# OECU_BASE1.net
KiCad netlist of a schematic drawn in Altium Designer
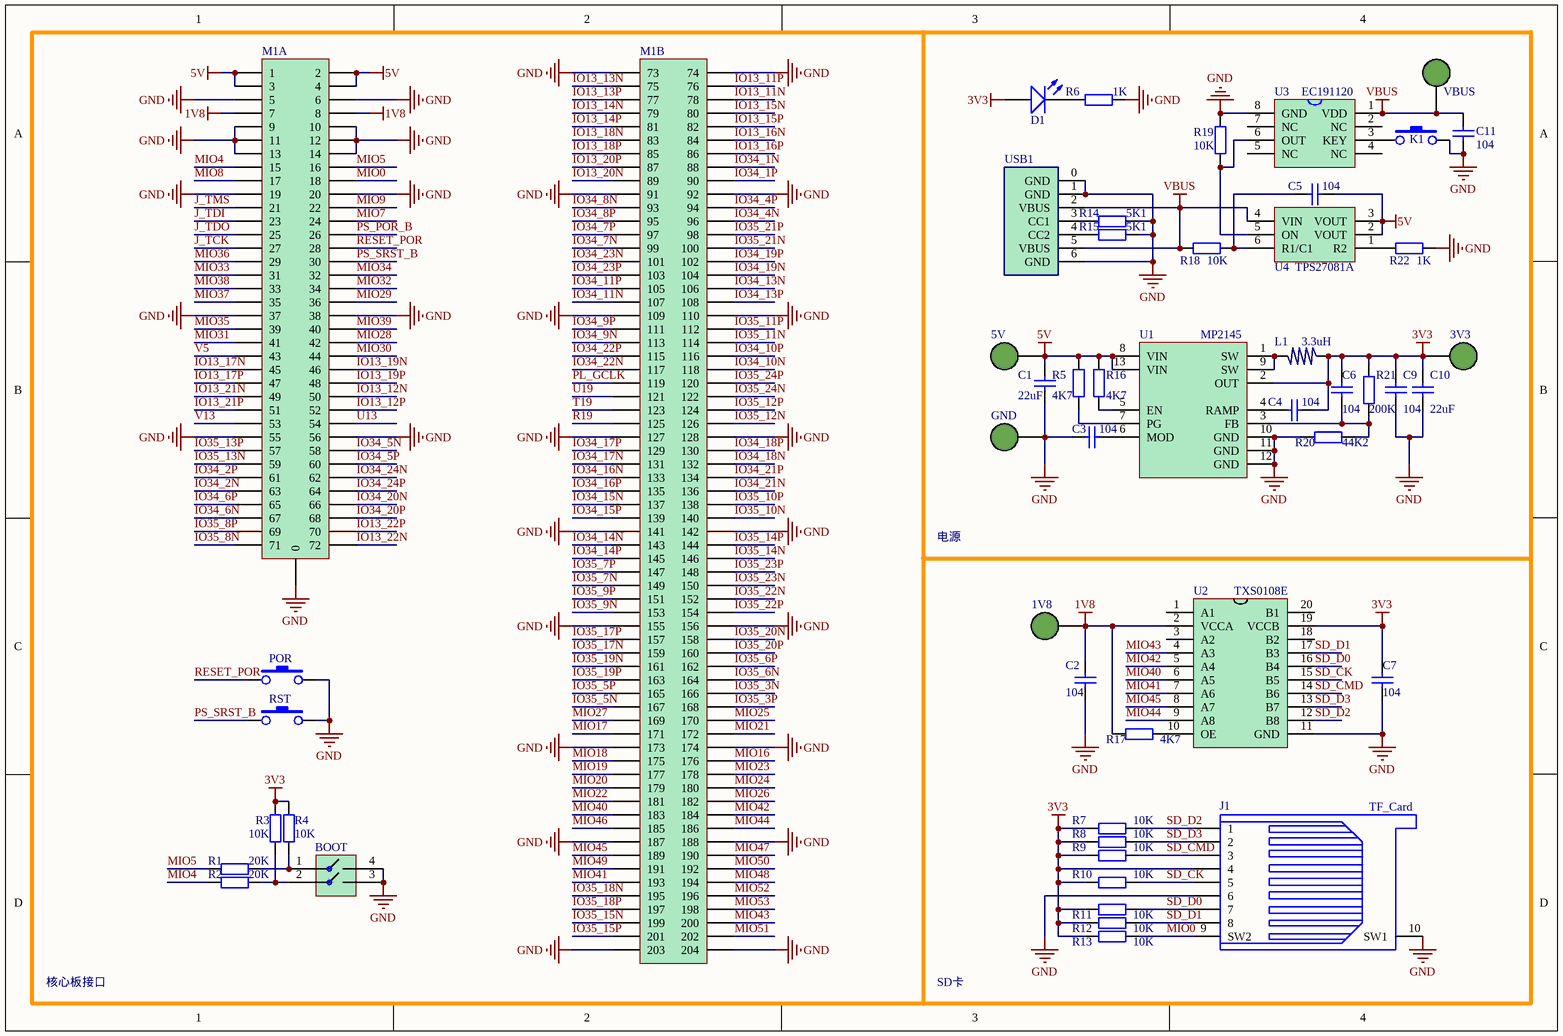
[diagram p0: OECU_BASE1.SchDoc]

(export (version "E")
  (design (tool "Eeschema 10.0.6"))
  (components
    (comp (ref "1V8")
      (value "TEST_POINT_2mm")
      (footprint "TEST_POINT_2mm")
      (libsource (lib "MT_Connector") (part "TEST_POINT_2mm"))
    )
    (comp (ref "3V3")
      (value "TEST_POINT_2mm")
      (footprint "TEST_POINT_2mm")
      (libsource (lib "MT_Connector") (part "TEST_POINT_2mm"))
    )
    (comp (ref "5V")
      (value "TEST_POINT_2mm")
      (footprint "TEST_POINT_2mm")
      (libsource (lib "MT_Connector") (part "TEST_POINT_2mm"))
    )
    (comp (ref "BOOT")
      (value "DIP_SWITCH_2.54_2_SMD_S")
      (footprint "DIP_SWITCH_2.54_2_SMD_S")
      (description "双路贴片立式拨码开关")
      (libsource (lib "MT_Device") (part "DIP_SWITCH_2.54_2_SMD_S"))
    )
    (comp (ref "C1")
      (value "22uF")
      (footprint "1206")
      (description "贴片电容 1206")
      (libsource (lib "MT_Device") (part "CAP_1206"))
    )
    (comp (ref "C2")
      (value "104")
      (footprint "0402")
      (description "贴片电容 0402")
      (libsource (lib "MT_Device") (part "CAP_0402"))
    )
    (comp (ref "C3")
      (value "104")
      (footprint "0402")
      (description "贴片电容 0402")
      (libsource (lib "MT_Device") (part "CAP_0402"))
    )
    (comp (ref "C4")
      (value "104")
      (footprint "0402")
      (description "贴片电容 0402")
      (libsource (lib "MT_Device") (part "CAP_0402"))
    )
    (comp (ref "C5")
      (value "104")
      (footprint "0402")
      (description "贴片电容 0402")
      (libsource (lib "MT_Device") (part "CAP_0402"))
    )
    (comp (ref "C6")
      (value "104")
      (footprint "0402")
      (description "贴片电容 0402")
      (libsource (lib "MT_Device") (part "CAP_0402"))
    )
    (comp (ref "C7")
      (value "104")
      (footprint "0402")
      (description "贴片电容 0402")
      (libsource (lib "MT_Device") (part "CAP_0402"))
    )
    (comp (ref "C9")
      (value "104")
      (footprint "0402")
      (description "贴片电容 0402")
      (libsource (lib "MT_Device") (part "CAP_0402"))
    )
    (comp (ref "C10")
      (value "22uF")
      (footprint "1206")
      (description "贴片电容 1206")
      (libsource (lib "MT_Device") (part "CAP_1206"))
    )
    (comp (ref "C11")
      (value "104")
      (footprint "0402")
      (description "贴片电容 0402")
      (libsource (lib "MT_Device") (part "CAP_0402"))
    )
    (comp (ref "D1")
      (value "LED")
      (footprint "LED_0603")
      (description "LED 0603")
      (libsource (lib "MT_Device") (part "LED_0603"))
    )
    (comp (ref "GND")
      (value "TEST_POINT_2mm")
      (footprint "TEST_POINT_2mm")
      (libsource (lib "MT_Connector") (part "TEST_POINT_2mm"))
    )
    (comp (ref "J1")
      (value "TF_Card")
      (footprint "TF_card")
      (description "TF卡座")
      (libsource (lib "MT_Device") (part "TF_Card"))
    )
    (comp (ref "K1")
      (value "KEY")
      (footprint "KEY_DIP_6_L")
      (description "直插卧式按键 6mm")
      (libsource (lib "MT_Device") (part "KEY_DIP_6_L"))
    )
    (comp (ref "L1")
      (value "3.3uH")
      (footprint "L_0420")
      (description "电感 0420")
      (libsource (lib "MT_Device") (part "L_0420"))
    )
    (comp (ref "M1")
      (value "DDR3_204P_H8")
      (footprint "DDR3_204P_H8")
      (libsource (lib "MT_Connector") (part "DDR3_204P_H8"))
    )
    (comp (ref "POR")
      (value "KEY")
      (footprint "KEY_DIP_6_L")
      (description "直插卧式按键 6mm")
      (libsource (lib "MT_Device") (part "KEY_DIP_6_L"))
    )
    (comp (ref "R1")
      (value "20K")
      (footprint "R_0402")
      (description "电阻 0402")
      (libsource (lib "") (part "RES_0402_1"))
    )
    (comp (ref "R2")
      (value "20K")
      (footprint "R_0402")
      (description "电阻 0402")
      (libsource (lib "") (part "RES_0402_1"))
    )
    (comp (ref "R3")
      (value "10K")
      (footprint "R_0402")
      (description "电阻 0402")
      (libsource (lib "") (part "RES_0402_2"))
    )
    (comp (ref "R4")
      (value "10K")
      (footprint "R_0402")
      (description "电阻 0402")
      (libsource (lib "") (part "RES_0402_2"))
    )
    (comp (ref "R5")
      (value "4K7")
      (footprint "R_0402")
      (description "电阻 0402")
      (libsource (lib "") (part "RES_0402_2"))
    )
    (comp (ref "R6")
      (value "1K")
      (footprint "R_0402")
      (description "电阻 0402")
      (libsource (lib "MT_Device") (part "RES_0402"))
    )
    (comp (ref "R7")
      (value "10K")
      (footprint "R_0402")
      (description "电阻 0402")
      (libsource (lib "MT_Device") (part "RES_0402"))
    )
    (comp (ref "R8")
      (value "10K")
      (footprint "R_0402")
      (description "电阻 0402")
      (libsource (lib "MT_Device") (part "RES_0402"))
    )
    (comp (ref "R9")
      (value "10K")
      (footprint "R_0402")
      (description "电阻 0402")
      (libsource (lib "MT_Device") (part "RES_0402"))
    )
    (comp (ref "R10")
      (value "10K")
      (footprint "R_0402")
      (description "电阻 0402")
      (libsource (lib "MT_Device") (part "RES_0402"))
    )
    (comp (ref "R11")
      (value "10K")
      (footprint "R_0402")
      (description "电阻 0402")
      (libsource (lib "MT_Device") (part "RES_0402"))
    )
    (comp (ref "R12")
      (value "10K")
      (footprint "R_0402")
      (description "电阻 0402")
      (libsource (lib "MT_Device") (part "RES_0402"))
    )
    (comp (ref "R13")
      (value "10K")
      (footprint "R_0402")
      (description "电阻 0402")
      (libsource (lib "MT_Device") (part "RES_0402"))
    )
    (comp (ref "R14")
      (value "5K1")
      (footprint "R_0402")
      (description "电阻 0402")
      (libsource (lib "") (part "RES_0402_1"))
    )
    (comp (ref "R15")
      (value "5K1")
      (footprint "R_0402")
      (description "电阻 0402")
      (libsource (lib "") (part "RES_0402_1"))
    )
    (comp (ref "R16")
      (value "4K7")
      (footprint "R_0402")
      (description "电阻 0402")
      (libsource (lib "") (part "RES_0402_2"))
    )
    (comp (ref "R17")
      (value "4K7")
      (footprint "R_0402")
      (description "电阻 0402")
      (libsource (lib "MT_Device") (part "RES_0402"))
    )
    (comp (ref "R18")
      (value "10K")
      (footprint "R_0402")
      (description "电阻 0402")
      (libsource (lib "") (part "RES_0402_1"))
    )
    (comp (ref "R19")
      (value "10K")
      (footprint "R_0402")
      (description "电阻 0402")
      (libsource (lib "") (part "RES_0402_2"))
    )
    (comp (ref "R20")
      (value "44K2")
      (footprint "R_0402")
      (description "电阻 0402")
      (libsource (lib "") (part "RES_0402_1"))
    )
    (comp (ref "R21")
      (value "200K")
      (footprint "R_0402")
      (description "电阻 0402")
      (libsource (lib "") (part "RES_0402_2"))
    )
    (comp (ref "R22")
      (value "1K")
      (footprint "R_0402")
      (description "电阻 0402")
      (libsource (lib "MT_Device") (part "RES_0402"))
    )
    (comp (ref "RST")
      (value "KEY")
      (footprint "KEY_DIP_6_L")
      (description "直插卧式按键 6mm")
      (libsource (lib "MT_Device") (part "KEY_DIP_6_L"))
    )
    (comp (ref "U1")
      (value "MP2145")
      (footprint "QFN12")
      (description "5.5V, 6A, 1.2MHz")
      (libsource (lib "MT_Chip") (part "MP2145"))
    )
    (comp (ref "U2") (value "TXS0108E") (footprint "TSSOP20") (libsource (lib "MT_Chip") (part "TXS0108E")))
    (comp (ref "U3")
      (value "EC191120")
      (footprint "SOP8-150MIL")
      (description "长按2秒开关机")
      (libsource (lib "MT_Chip") (part "EC191120"))
    )
    (comp (ref "U4")
      (value "TPS27081A")
      (footprint "SOT_23_6")
      (description "高侧负载开关")
      (libsource (lib "MT_Chip") (part "TPS27081A"))
    )
    (comp (ref "USB1")
      (value "USB_C_6P")
      (footprint "USB_C_6PIN")
      (libsource (lib "MT_Device") (part "USB_C_6P"))
    )
    (comp (ref "VBUS")
      (value "TEST_POINT_2mm")
      (footprint "TEST_POINT_2mm")
      (libsource (lib "MT_Connector") (part "TEST_POINT_2mm"))
    )
  )
  (nets
    (net (code "1") (name "/IO13_11N") (class "Default")
      (node (ref "M1") (pin "78") (pinfunction "78_78") (pintype "passive"))
    )
    (net (code "2") (name "/IO13_11P") (class "Default")
      (node (ref "M1") (pin "76") (pinfunction "76_76") (pintype "passive"))
    )
    (net (code "3") (name "/IO13_12N") (class "Default")
      (node (ref "M1") (pin "50") (pinfunction "50_50") (pintype "passive"))
    )
    (net (code "4") (name "/IO13_12P") (class "Default")
      (node (ref "M1") (pin "52") (pinfunction "52_52") (pintype "passive"))
    )
    (net (code "5") (name "/IO13_13N") (class "Default")
      (node (ref "M1") (pin "75") (pinfunction "75_75") (pintype "passive"))
    )
    (net (code "6") (name "/IO13_13P") (class "Default")
      (node (ref "M1") (pin "77") (pinfunction "77_77") (pintype "passive"))
    )
    (net (code "7") (name "/IO13_14N") (class "Default")
      (node (ref "M1") (pin "79") (pinfunction "79_79") (pintype "passive"))
    )
    (net (code "8") (name "/IO13_14P") (class "Default")
      (node (ref "M1") (pin "81") (pinfunction "81_81") (pintype "passive"))
    )
    (net (code "9") (name "/IO13_15N") (class "Default")
      (node (ref "M1") (pin "80") (pinfunction "80_80") (pintype "passive"))
    )
    (net (code "10") (name "/IO13_15P") (class "Default")
      (node (ref "M1") (pin "82") (pinfunction "82_82") (pintype "passive"))
    )
    (net (code "11") (name "/IO13_16N") (class "Default")
      (node (ref "M1") (pin "84") (pinfunction "84_84") (pintype "passive"))
    )
    (net (code "12") (name "/IO13_16P") (class "Default")
      (node (ref "M1") (pin "86") (pinfunction "86_86") (pintype "passive"))
    )
    (net (code "13") (name "/IO13_17N") (class "Default")
      (node (ref "M1") (pin "45") (pinfunction "45_45") (pintype "passive"))
    )
    (net (code "14") (name "/IO13_17P") (class "Default")
      (node (ref "M1") (pin "47") (pinfunction "47_47") (pintype "passive"))
    )
    (net (code "15") (name "/IO13_18N") (class "Default")
      (node (ref "M1") (pin "83") (pinfunction "83_83") (pintype "passive"))
    )
    (net (code "16") (name "/IO13_18P") (class "Default")
      (node (ref "M1") (pin "85") (pinfunction "85_85") (pintype "passive"))
    )
    (net (code "17") (name "/IO13_19N") (class "Default")
      (node (ref "M1") (pin "46") (pinfunction "46_46") (pintype "passive"))
    )
    (net (code "18") (name "/IO13_19P") (class "Default")
      (node (ref "M1") (pin "48") (pinfunction "48_48") (pintype "passive"))
    )
    (net (code "19") (name "/IO13_20N") (class "Default")
      (node (ref "M1") (pin "89") (pinfunction "89_89") (pintype "passive"))
    )
    (net (code "20") (name "/IO13_20P") (class "Default")
      (node (ref "M1") (pin "87") (pinfunction "87_87") (pintype "passive"))
    )
    (net (code "21") (name "/IO13_21N") (class "Default")
      (node (ref "M1") (pin "49") (pinfunction "49_49") (pintype "passive"))
    )
    (net (code "22") (name "/IO13_21P") (class "Default")
      (node (ref "M1") (pin "51") (pinfunction "51_51") (pintype "passive"))
    )
    (net (code "23") (name "/IO13_22N") (class "Default")
      (node (ref "M1") (pin "72") (pinfunction "72_72") (pintype "passive"))
    )
    (net (code "24") (name "/IO13_22P") (class "Default")
      (node (ref "M1") (pin "70") (pinfunction "70_70") (pintype "passive"))
    )
    (net (code "25") (name "/IO34_1N") (class "Default")
      (node (ref "M1") (pin "88") (pinfunction "88_88") (pintype "passive"))
    )
    (net (code "26") (name "/IO34_1P") (class "Default")
      (node (ref "M1") (pin "90") (pinfunction "90_90") (pintype "passive"))
    )
    (net (code "27") (name "/IO34_2N") (class "Default")
      (node (ref "M1") (pin "63") (pinfunction "63_63") (pintype "passive"))
    )
    (net (code "28") (name "/IO34_2P") (class "Default")
      (node (ref "M1") (pin "61") (pinfunction "61_61") (pintype "passive"))
    )
    (net (code "29") (name "/IO34_4N") (class "Default")
      (node (ref "M1") (pin "96") (pinfunction "96_96") (pintype "passive"))
    )
    (net (code "30") (name "/IO34_4P") (class "Default")
      (node (ref "M1") (pin "94") (pinfunction "94_94") (pintype "passive"))
    )
    (net (code "31") (name "/IO34_5N") (class "Default")
      (node (ref "M1") (pin "58") (pinfunction "58_58") (pintype "passive"))
    )
    (net (code "32") (name "/IO34_5P") (class "Default")
      (node (ref "M1") (pin "60") (pinfunction "60_60") (pintype "passive"))
    )
    (net (code "33") (name "/IO34_6N") (class "Default")
      (node (ref "M1") (pin "67") (pinfunction "67_67") (pintype "passive"))
    )
    (net (code "34") (name "/IO34_6P") (class "Default")
      (node (ref "M1") (pin "65") (pinfunction "65_65") (pintype "passive"))
    )
    (net (code "35") (name "/IO34_7N") (class "Default")
      (node (ref "M1") (pin "99") (pinfunction "99_99") (pintype "passive"))
    )
    (net (code "36") (name "/IO34_7P") (class "Default")
      (node (ref "M1") (pin "97") (pinfunction "97_97") (pintype "passive"))
    )
    (net (code "37") (name "/IO34_8N") (class "Default")
      (node (ref "M1") (pin "93") (pinfunction "93_93") (pintype "passive"))
    )
    (net (code "38") (name "/IO34_8P") (class "Default")
      (node (ref "M1") (pin "95") (pinfunction "95_95") (pintype "passive"))
    )
    (net (code "39") (name "/IO34_9N") (class "Default")
      (node (ref "M1") (pin "113") (pinfunction "113_113") (pintype "passive"))
    )
    (net (code "40") (name "/IO34_9P") (class "Default")
      (node (ref "M1") (pin "111") (pinfunction "111_111") (pintype "passive"))
    )
    (net (code "41") (name "/IO34_10N") (class "Default")
      (node (ref "M1") (pin "118") (pinfunction "118_118") (pintype "passive"))
    )
    (net (code "42") (name "/IO34_10P") (class "Default")
      (node (ref "M1") (pin "116") (pinfunction "116_116") (pintype "passive"))
    )
    (net (code "43") (name "/IO34_11N") (class "Default")
      (node (ref "M1") (pin "107") (pinfunction "107_107") (pintype "passive"))
    )
    (net (code "44") (name "/IO34_11P") (class "Default")
      (node (ref "M1") (pin "105") (pinfunction "105_105") (pintype "passive"))
    )
    (net (code "45") (name "/IO34_13N") (class "Default")
      (node (ref "M1") (pin "106") (pinfunction "106_106") (pintype "passive"))
    )
    (net (code "46") (name "/IO34_13P") (class "Default")
      (node (ref "M1") (pin "108") (pinfunction "108_108") (pintype "passive"))
    )
    (net (code "47") (name "/IO34_14N") (class "Default")
      (node (ref "M1") (pin "143") (pinfunction "143_143") (pintype "passive"))
    )
    (net (code "48") (name "/IO34_14P") (class "Default")
      (node (ref "M1") (pin "145") (pinfunction "145_145") (pintype "passive"))
    )
    (net (code "49") (name "/IO34_15N") (class "Default")
      (node (ref "M1") (pin "137") (pinfunction "137_137") (pintype "passive"))
    )
    (net (code "50") (name "/IO34_15P") (class "Default")
      (node (ref "M1") (pin "139") (pinfunction "139_139") (pintype "passive"))
    )
    (net (code "51") (name "/IO34_16N") (class "Default")
      (node (ref "M1") (pin "133") (pinfunction "133_133") (pintype "passive"))
    )
    (net (code "52") (name "/IO34_16P") (class "Default")
      (node (ref "M1") (pin "135") (pinfunction "135_135") (pintype "passive"))
    )
    (net (code "53") (name "/IO34_17N") (class "Default")
      (node (ref "M1") (pin "131") (pinfunction "131_131") (pintype "passive"))
    )
    (net (code "54") (name "/IO34_17P") (class "Default")
      (node (ref "M1") (pin "129") (pinfunction "129_129") (pintype "passive"))
    )
    (net (code "55") (name "/IO34_18N") (class "Default")
      (node (ref "M1") (pin "132") (pinfunction "132_132") (pintype "passive"))
    )
    (net (code "56") (name "/IO34_18P") (class "Default")
      (node (ref "M1") (pin "130") (pinfunction "130_130") (pintype "passive"))
    )
    (net (code "57") (name "/IO34_19N") (class "Default")
      (node (ref "M1") (pin "104") (pinfunction "104_104") (pintype "passive"))
    )
    (net (code "58") (name "/IO34_19P") (class "Default")
      (node (ref "M1") (pin "102") (pinfunction "102_102") (pintype "passive"))
    )
    (net (code "59") (name "/IO34_20N") (class "Default")
      (node (ref "M1") (pin "66") (pinfunction "66_66") (pintype "passive"))
    )
    (net (code "60") (name "/IO34_20P") (class "Default")
      (node (ref "M1") (pin "68") (pinfunction "68_68") (pintype "passive"))
    )
    (net (code "61") (name "/IO34_21N") (class "Default")
      (node (ref "M1") (pin "136") (pinfunction "136_136") (pintype "passive"))
    )
    (net (code "62") (name "/IO34_21P") (class "Default")
      (node (ref "M1") (pin "134") (pinfunction "134_134") (pintype "passive"))
    )
    (net (code "63") (name "/IO34_22N") (class "Default")
      (node (ref "M1") (pin "117") (pinfunction "117_117") (pintype "passive"))
    )
    (net (code "64") (name "/IO34_22P") (class "Default")
      (node (ref "M1") (pin "115") (pinfunction "115_115") (pintype "passive"))
    )
    (net (code "65") (name "/IO34_23N") (class "Default")
      (node (ref "M1") (pin "101") (pinfunction "101_101") (pintype "passive"))
    )
    (net (code "66") (name "/IO34_23P") (class "Default")
      (node (ref "M1") (pin "103") (pinfunction "103_103") (pintype "passive"))
    )
    (net (code "67") (name "/IO34_24N") (class "Default")
      (node (ref "M1") (pin "62") (pinfunction "62_62") (pintype "passive"))
    )
    (net (code "68") (name "/IO34_24P") (class "Default")
      (node (ref "M1") (pin "64") (pinfunction "64_64") (pintype "passive"))
    )
    (net (code "69") (name "/IO35_3N") (class "Default")
      (node (ref "M1") (pin "166") (pinfunction "166_166") (pintype "passive"))
    )
    (net (code "70") (name "/IO35_3P") (class "Default")
      (node (ref "M1") (pin "168") (pinfunction "168_168") (pintype "passive"))
    )
    (net (code "71") (name "/IO35_5N") (class "Default")
      (node (ref "M1") (pin "167") (pinfunction "167_167") (pintype "passive"))
    )
    (net (code "72") (name "/IO35_5P") (class "Default")
      (node (ref "M1") (pin "165") (pinfunction "165_165") (pintype "passive"))
    )
    (net (code "73") (name "/IO35_6N") (class "Default")
      (node (ref "M1") (pin "164") (pinfunction "164_164") (pintype "passive"))
    )
    (net (code "74") (name "/IO35_6P") (class "Default")
      (node (ref "M1") (pin "162") (pinfunction "162_162") (pintype "passive"))
    )
    (net (code "75") (name "/IO35_7N") (class "Default")
      (node (ref "M1") (pin "149") (pinfunction "149_149") (pintype "passive"))
    )
    (net (code "76") (name "/IO35_7P") (class "Default")
      (node (ref "M1") (pin "147") (pinfunction "147_147") (pintype "passive"))
    )
    (net (code "77") (name "/IO35_8N") (class "Default")
      (node (ref "M1") (pin "71") (pinfunction "71_71") (pintype "passive"))
    )
    (net (code "78") (name "/IO35_8P") (class "Default")
      (node (ref "M1") (pin "69") (pinfunction "69_69") (pintype "passive"))
    )
    (net (code "79") (name "/IO35_9N") (class "Default")
      (node (ref "M1") (pin "153") (pinfunction "153_153") (pintype "passive"))
    )
    (net (code "80") (name "/IO35_9P") (class "Default")
      (node (ref "M1") (pin "151") (pinfunction "151_151") (pintype "passive"))
    )
    (net (code "81") (name "/IO35_10N") (class "Default")
      (node (ref "M1") (pin "140") (pinfunction "140_140") (pintype "passive"))
    )
    (net (code "82") (name "/IO35_10P") (class "Default")
      (node (ref "M1") (pin "138") (pinfunction "138_138") (pintype "passive"))
    )
    (net (code "83") (name "/IO35_11N") (class "Default")
      (node (ref "M1") (pin "114") (pinfunction "114_114") (pintype "passive"))
    )
    (net (code "84") (name "/IO35_11P") (class "Default")
      (node (ref "M1") (pin "112") (pinfunction "112_112") (pintype "passive"))
    )
    (net (code "85") (name "/IO35_12N") (class "Default")
      (node (ref "M1") (pin "126") (pinfunction "126_126") (pintype "passive"))
    )
    (net (code "86") (name "/IO35_12P") (class "Default")
      (node (ref "M1") (pin "124") (pinfunction "124_124") (pintype "passive"))
    )
    (net (code "87") (name "/IO35_13N") (class "Default")
      (node (ref "M1") (pin "59") (pinfunction "59_59") (pintype "passive"))
    )
    (net (code "88") (name "/IO35_13P") (class "Default")
      (node (ref "M1") (pin "57") (pinfunction "57_57") (pintype "passive"))
    )
    (net (code "89") (name "/IO35_14N") (class "Default")
      (node (ref "M1") (pin "146") (pinfunction "146_146") (pintype "passive"))
    )
    (net (code "90") (name "/IO35_14P") (class "Default")
      (node (ref "M1") (pin "144") (pinfunction "144_144") (pintype "passive"))
    )
    (net (code "91") (name "/IO35_15N") (class "Default")
      (node (ref "M1") (pin "199") (pinfunction "199_199") (pintype "passive"))
    )
    (net (code "92") (name "/IO35_15P") (class "Default")
      (node (ref "M1") (pin "201") (pinfunction "201_201") (pintype "passive"))
    )
    (net (code "93") (name "/IO35_17N") (class "Default")
      (node (ref "M1") (pin "159") (pinfunction "159_159") (pintype "passive"))
    )
    (net (code "94") (name "/IO35_17P") (class "Default")
      (node (ref "M1") (pin "157") (pinfunction "157_157") (pintype "passive"))
    )
    (net (code "95") (name "/IO35_18N") (class "Default")
      (node (ref "M1") (pin "195") (pinfunction "195_195") (pintype "passive"))
    )
    (net (code "96") (name "/IO35_18P") (class "Default")
      (node (ref "M1") (pin "197") (pinfunction "197_197") (pintype "passive"))
    )
    (net (code "97") (name "/IO35_19N") (class "Default")
      (node (ref "M1") (pin "161") (pinfunction "161_161") (pintype "passive"))
    )
    (net (code "98") (name "/IO35_19P") (class "Default")
      (node (ref "M1") (pin "163") (pinfunction "163_163") (pintype "passive"))
    )
    (net (code "99") (name "/IO35_20N") (class "Default")
      (node (ref "M1") (pin "158") (pinfunction "158_158") (pintype "passive"))
    )
    (net (code "100") (name "/IO35_20P") (class "Default")
      (node (ref "M1") (pin "160") (pinfunction "160_160") (pintype "passive"))
    )
    (net (code "101") (name "/IO35_21N") (class "Default")
      (node (ref "M1") (pin "100") (pinfunction "100_100") (pintype "passive"))
    )
    (net (code "102") (name "/IO35_21P") (class "Default")
      (node (ref "M1") (pin "98") (pinfunction "98_98") (pintype "passive"))
    )
    (net (code "103") (name "/IO35_22N") (class "Default")
      (node (ref "M1") (pin "152") (pinfunction "152_152") (pintype "passive"))
    )
    (net (code "104") (name "/IO35_22P") (class "Default")
      (node (ref "M1") (pin "154") (pinfunction "154_154") (pintype "passive"))
    )
    (net (code "105") (name "/IO35_23N") (class "Default")
      (node (ref "M1") (pin "150") (pinfunction "150_150") (pintype "passive"))
    )
    (net (code "106") (name "/IO35_23P") (class "Default")
      (node (ref "M1") (pin "148") (pinfunction "148_148") (pintype "passive"))
    )
    (net (code "107") (name "/IO35_24N") (class "Default")
      (node (ref "M1") (pin "122") (pinfunction "122_122") (pintype "passive"))
    )
    (net (code "108") (name "/IO35_24P") (class "Default")
      (node (ref "M1") (pin "120") (pinfunction "120_120") (pintype "passive"))
    )
    (net (code "109") (name "/J_TCK") (class "Default")
      (node (ref "M1") (pin "27") (pinfunction "27_27") (pintype "passive"))
    )
    (net (code "110") (name "/J_TDI") (class "Default")
      (node (ref "M1") (pin "23") (pinfunction "23_23") (pintype "passive"))
    )
    (net (code "111") (name "/J_TDO") (class "Default")
      (node (ref "M1") (pin "25") (pinfunction "25_25") (pintype "passive"))
    )
    (net (code "112") (name "/J_TMS") (class "Default")
      (node (ref "M1") (pin "21") (pinfunction "21_21") (pintype "passive"))
    )
    (net (code "113") (name "/MIO0") (class "Default")
      (node (ref "J1") (pin "9") (pinfunction "SW2_9") (pintype "passive"))
      (node (ref "M1") (pin "18") (pinfunction "18_18") (pintype "passive"))
      (node (ref "R13") (pin "2") (pinfunction "2_2") (pintype "passive"))
    )
    (net (code "114") (name "/MIO4") (class "Default")
      (node (ref "M1") (pin "15") (pinfunction "15_15") (pintype "passive"))
      (node (ref "R2") (pin "2") (pinfunction "2_2") (pintype "passive"))
    )
    (net (code "115") (name "/MIO5") (class "Default")
      (node (ref "M1") (pin "16") (pinfunction "16_16") (pintype "passive"))
      (node (ref "R1") (pin "2") (pinfunction "2_2") (pintype "passive"))
    )
    (net (code "116") (name "/MIO7") (class "Default")
      (node (ref "M1") (pin "24") (pinfunction "24_24") (pintype "passive"))
    )
    (net (code "117") (name "/MIO8") (class "Default")
      (node (ref "M1") (pin "17") (pinfunction "17_17") (pintype "passive"))
    )
    (net (code "118") (name "/MIO9") (class "Default")
      (node (ref "M1") (pin "22") (pinfunction "22_22") (pintype "passive"))
    )
    (net (code "119") (name "/MIO16") (class "Default")
      (node (ref "M1") (pin "176") (pinfunction "176_176") (pintype "passive"))
    )
    (net (code "120") (name "/MIO17") (class "Default")
      (node (ref "M1") (pin "171") (pinfunction "171_171") (pintype "passive"))
    )
    (net (code "121") (name "/MIO18") (class "Default")
      (node (ref "M1") (pin "175") (pinfunction "175_175") (pintype "passive"))
    )
    (net (code "122") (name "/MIO19") (class "Default")
      (node (ref "M1") (pin "177") (pinfunction "177_177") (pintype "passive"))
    )
    (net (code "123") (name "/MIO20") (class "Default")
      (node (ref "M1") (pin "179") (pinfunction "179_179") (pintype "passive"))
    )
    (net (code "124") (name "/MIO21") (class "Default")
      (node (ref "M1") (pin "172") (pinfunction "172_172") (pintype "passive"))
    )
    (net (code "125") (name "/MIO22") (class "Default")
      (node (ref "M1") (pin "181") (pinfunction "181_181") (pintype "passive"))
    )
    (net (code "126") (name "/MIO23") (class "Default")
      (node (ref "M1") (pin "178") (pinfunction "178_178") (pintype "passive"))
    )
    (net (code "127") (name "/MIO24") (class "Default")
      (node (ref "M1") (pin "180") (pinfunction "180_180") (pintype "passive"))
    )
    (net (code "128") (name "/MIO25") (class "Default")
      (node (ref "M1") (pin "170") (pinfunction "170_170") (pintype "passive"))
    )
    (net (code "129") (name "/MIO26") (class "Default")
      (node (ref "M1") (pin "182") (pinfunction "182_182") (pintype "passive"))
    )
    (net (code "130") (name "/MIO27") (class "Default")
      (node (ref "M1") (pin "169") (pinfunction "169_169") (pintype "passive"))
    )
    (net (code "131") (name "/MIO28") (class "Default")
      (node (ref "M1") (pin "42") (pinfunction "42_42") (pintype "passive"))
    )
    (net (code "132") (name "/MIO29") (class "Default")
      (node (ref "M1") (pin "36") (pinfunction "36_36") (pintype "passive"))
    )
    (net (code "133") (name "/MIO30") (class "Default")
      (node (ref "M1") (pin "44") (pinfunction "44_44") (pintype "passive"))
    )
    (net (code "134") (name "/MIO31") (class "Default")
      (node (ref "M1") (pin "41") (pinfunction "41_41") (pintype "passive"))
    )
    (net (code "135") (name "/MIO32") (class "Default")
      (node (ref "M1") (pin "34") (pinfunction "34_34") (pintype "passive"))
    )
    (net (code "136") (name "/MIO33") (class "Default")
      (node (ref "M1") (pin "31") (pinfunction "31_31") (pintype "passive"))
    )
    (net (code "137") (name "/MIO34") (class "Default")
      (node (ref "M1") (pin "32") (pinfunction "32_32") (pintype "passive"))
    )
    (net (code "138") (name "/MIO35") (class "Default")
      (node (ref "M1") (pin "39") (pinfunction "39_39") (pintype "passive"))
    )
    (net (code "139") (name "/MIO36") (class "Default")
      (node (ref "M1") (pin "29") (pinfunction "29_29") (pintype "passive"))
    )
    (net (code "140") (name "/MIO37") (class "Default")
      (node (ref "M1") (pin "35") (pinfunction "35_35") (pintype "passive"))
    )
    (net (code "141") (name "/MIO38") (class "Default")
      (node (ref "M1") (pin "33") (pinfunction "33_33") (pintype "passive"))
    )
    (net (code "142") (name "/MIO39") (class "Default")
      (node (ref "M1") (pin "40") (pinfunction "40_40") (pintype "passive"))
    )
    (net (code "143") (name "/MIO40") (class "Default")
      (node (ref "M1") (pin "183") (pinfunction "183_183") (pintype "passive"))
      (node (ref "U2") (pin "6") (pinfunction "A5_6") (pintype "passive"))
    )
    (net (code "144") (name "/MIO41") (class "Default")
      (node (ref "M1") (pin "193") (pinfunction "193_193") (pintype "passive"))
      (node (ref "U2") (pin "7") (pinfunction "A6_7") (pintype "passive"))
    )
    (net (code "145") (name "/MIO42") (class "Default")
      (node (ref "M1") (pin "184") (pinfunction "184_184") (pintype "passive"))
      (node (ref "U2") (pin "5") (pinfunction "A4_5") (pintype "passive"))
    )
    (net (code "146") (name "/MIO43") (class "Default")
      (node (ref "M1") (pin "200") (pinfunction "200_200") (pintype "passive"))
      (node (ref "U2") (pin "4") (pinfunction "A3_4") (pintype "passive"))
    )
    (net (code "147") (name "/MIO44") (class "Default")
      (node (ref "M1") (pin "186") (pinfunction "186_186") (pintype "passive"))
      (node (ref "U2") (pin "9") (pinfunction "A8_9") (pintype "passive"))
    )
    (net (code "148") (name "/MIO45") (class "Default")
      (node (ref "M1") (pin "189") (pinfunction "189_189") (pintype "passive"))
      (node (ref "U2") (pin "8") (pinfunction "A7_8") (pintype "passive"))
    )
    (net (code "149") (name "/MIO46") (class "Default")
      (node (ref "M1") (pin "185") (pinfunction "185_185") (pintype "passive"))
    )
    (net (code "150") (name "/MIO47") (class "Default")
      (node (ref "M1") (pin "190") (pinfunction "190_190") (pintype "passive"))
    )
    (net (code "151") (name "/MIO48") (class "Default")
      (node (ref "M1") (pin "194") (pinfunction "194_194") (pintype "passive"))
    )
    (net (code "152") (name "/MIO49") (class "Default")
      (node (ref "M1") (pin "191") (pinfunction "191_191") (pintype "passive"))
    )
    (net (code "153") (name "/MIO50") (class "Default")
      (node (ref "M1") (pin "192") (pinfunction "192_192") (pintype "passive"))
    )
    (net (code "154") (name "/MIO51") (class "Default")
      (node (ref "M1") (pin "202") (pinfunction "202_202") (pintype "passive"))
    )
    (net (code "155") (name "/MIO52") (class "Default")
      (node (ref "M1") (pin "196") (pinfunction "196_196") (pintype "passive"))
    )
    (net (code "156") (name "/MIO53") (class "Default")
      (node (ref "M1") (pin "198") (pinfunction "198_198") (pintype "passive"))
    )
    (net (code "157") (name "/PL_GCLK") (class "Default")
      (node (ref "M1") (pin "119") (pinfunction "119_119") (pintype "passive"))
    )
    (net (code "158") (name "/PS_POR_B") (class "Default")
      (node (ref "M1") (pin "26") (pinfunction "26_26") (pintype "passive"))
    )
    (net (code "159") (name "/PS_SRST_B") (class "Default")
      (node (ref "M1") (pin "30") (pinfunction "30_30") (pintype "passive"))
      (node (ref "RST") (pin "2") (pinfunction "2_2") (pintype "passive"))
    )
    (net (code "160") (name "/R19") (class "Default")
      (node (ref "M1") (pin "125") (pinfunction "125_125") (pintype "passive"))
    )
    (net (code "161") (name "/RESET_POR") (class "Default")
      (node (ref "M1") (pin "28") (pinfunction "28_28") (pintype "passive"))
      (node (ref "POR") (pin "2") (pinfunction "2_2") (pintype "passive"))
    )
    (net (code "162") (name "/SD_CK") (class "Default")
      (node (ref "J1") (pin "5") (pinfunction "5_5") (pintype "passive"))
      (node (ref "R10") (pin "2") (pinfunction "2_2") (pintype "passive"))
      (node (ref "U2") (pin "15") (pinfunction "B5_15") (pintype "passive"))
    )
    (net (code "163") (name "/SD_CMD") (class "Default")
      (node (ref "J1") (pin "3") (pinfunction "3_3") (pintype "passive"))
      (node (ref "R9") (pin "2") (pinfunction "2_2") (pintype "passive"))
      (node (ref "U2") (pin "14") (pinfunction "B6_14") (pintype "passive"))
    )
    (net (code "164") (name "/SD_D0") (class "Default")
      (node (ref "J1") (pin "7") (pinfunction "7_7") (pintype "passive"))
      (node (ref "R11") (pin "2") (pinfunction "2_2") (pintype "passive"))
      (node (ref "U2") (pin "16") (pinfunction "B4_16") (pintype "passive"))
    )
    (net (code "165") (name "/SD_D1") (class "Default")
      (node (ref "J1") (pin "8") (pinfunction "8_8") (pintype "passive"))
      (node (ref "R12") (pin "2") (pinfunction "2_2") (pintype "passive"))
      (node (ref "U2") (pin "17") (pinfunction "B3_17") (pintype "passive"))
    )
    (net (code "166") (name "/SD_D2") (class "Default")
      (node (ref "J1") (pin "1") (pinfunction "1_1") (pintype "passive"))
      (node (ref "R7") (pin "2") (pinfunction "2_2") (pintype "passive"))
      (node (ref "U2") (pin "12") (pinfunction "B8_12") (pintype "passive"))
    )
    (net (code "167") (name "/SD_D3") (class "Default")
      (node (ref "J1") (pin "2") (pinfunction "2_2") (pintype "passive"))
      (node (ref "R8") (pin "2") (pinfunction "2_2") (pintype "passive"))
      (node (ref "U2") (pin "13") (pinfunction "B7_13") (pintype "passive"))
    )
    (net (code "168") (name "/T19") (class "Default")
      (node (ref "M1") (pin "123") (pinfunction "123_123") (pintype "passive"))
    )
    (net (code "169") (name "/U13") (class "Default")
      (node (ref "M1") (pin "54") (pinfunction "54_54") (pintype "passive"))
    )
    (net (code "170") (name "/U19") (class "Default")
      (node (ref "M1") (pin "121") (pinfunction "121_121") (pintype "passive"))
    )
    (net (code "171") (name "/V5") (class "Default")
      (node (ref "M1") (pin "43") (pinfunction "43_43") (pintype "passive"))
    )
    (net (code "172") (name "/V13") (class "Default")
      (node (ref "M1") (pin "53") (pinfunction "53_53") (pintype "passive"))
    )
    (net (code "173") (name "1V8") (class "Default")
      (node (ref "1V8") (pin "1") (pinfunction "1_1") (pintype "passive"))
      (node (ref "C2") (pin "2") (pinfunction "2_2") (pintype "passive"))
      (node (ref "M1") (pin "7") (pinfunction "7_7") (pintype "passive"))
      (node (ref "M1") (pin "8") (pinfunction "8_8") (pintype "passive"))
      (node (ref "R17") (pin "1") (pinfunction "1_1") (pintype "passive"))
      (node (ref "U2") (pin "2") (pinfunction "VCCA_2") (pintype "passive"))
    )
    (net (code "174") (name "3V3") (class "Default")
      (node (ref "3V3") (pin "1") (pinfunction "1_1") (pintype "passive"))
      (node (ref "C10") (pin "2") (pinfunction "2_2") (pintype "passive"))
      (node (ref "C4") (pin "2") (pinfunction "2_2") (pintype "passive"))
      (node (ref "C6") (pin "2") (pinfunction "2_2") (pintype "passive"))
      (node (ref "C7") (pin "2") (pinfunction "2_2") (pintype "passive"))
      (node (ref "C9") (pin "2") (pinfunction "2_2") (pintype "passive"))
      (node (ref "D1") (pin "A") (pinfunction "A_A") (pintype "passive"))
      (node (ref "J1") (pin "4") (pinfunction "4_4") (pintype "passive"))
      (node (ref "L1") (pin "1") (pintype "passive"))
      (node (ref "R10") (pin "1") (pinfunction "1_1") (pintype "passive"))
      (node (ref "R11") (pin "1") (pinfunction "1_1") (pintype "passive"))
      (node (ref "R12") (pin "1") (pinfunction "1_1") (pintype "passive"))
      (node (ref "R13") (pin "1") (pinfunction "1_1") (pintype "passive"))
      (node (ref "R21") (pin "2") (pinfunction "2_2") (pintype "passive"))
      (node (ref "R3") (pin "2") (pinfunction "2_2") (pintype "passive"))
      (node (ref "R4") (pin "2") (pinfunction "2_2") (pintype "passive"))
      (node (ref "R7") (pin "1") (pinfunction "1_1") (pintype "passive"))
      (node (ref "R8") (pin "1") (pinfunction "1_1") (pintype "passive"))
      (node (ref "R9") (pin "1") (pinfunction "1_1") (pintype "passive"))
      (node (ref "U1") (pin "2") (pinfunction "OUT_2") (pintype "passive"))
      (node (ref "U2") (pin "19") (pinfunction "VCCB_19") (pintype "passive"))
    )
    (net (code "175") (name "5V") (class "Default")
      (node (ref "5V") (pin "1") (pinfunction "1_1") (pintype "passive"))
      (node (ref "C1") (pin "2") (pinfunction "2_2") (pintype "passive"))
      (node (ref "C5") (pin "1") (pinfunction "1_1") (pintype "passive"))
      (node (ref "M1") (pin "1") (pinfunction "1_1") (pintype "passive"))
      (node (ref "M1") (pin "2") (pinfunction "2_2") (pintype "passive"))
      (node (ref "M1") (pin "3") (pinfunction "3_3") (pintype "passive"))
      (node (ref "M1") (pin "4") (pinfunction "4_4") (pintype "passive"))
      (node (ref "R16") (pin "2") (pinfunction "2_2") (pintype "passive"))
      (node (ref "R5") (pin "2") (pinfunction "2_2") (pintype "passive"))
      (node (ref "U1") (pin "13") (pinfunction "VIN_13") (pintype "passive"))
      (node (ref "U1") (pin "8") (pinfunction "VIN_8") (pintype "passive"))
      (node (ref "U4") (pin "2") (pinfunction "VOUT_2") (pintype "passive"))
      (node (ref "U4") (pin "3") (pinfunction "VOUT_3") (pintype "passive"))
    )
    (net (code "176") (name "GND") (class "Default")
      (node (ref "BOOT") (pin "3") (pinfunction "3_3") (pintype "passive"))
      (node (ref "BOOT") (pin "4") (pinfunction "4_4") (pintype "passive"))
      (node (ref "C1") (pin "1") (pinfunction "1_1") (pintype "passive"))
      (node (ref "C10") (pin "1") (pinfunction "1_1") (pintype "passive"))
      (node (ref "C11") (pin "2") (pinfunction "2_2") (pintype "passive"))
      (node (ref "C2") (pin "1") (pinfunction "1_1") (pintype "passive"))
      (node (ref "C3") (pin "2") (pinfunction "2_2") (pintype "passive"))
      (node (ref "C7") (pin "1") (pinfunction "1_1") (pintype "passive"))
      (node (ref "C9") (pin "1") (pinfunction "1_1") (pintype "passive"))
      (node (ref "GND") (pin "1") (pinfunction "1_1") (pintype "passive"))
      (node (ref "J1") (pin "10") (pinfunction "SW1_10") (pintype "passive"))
      (node (ref "J1") (pin "6") (pinfunction "6_6") (pintype "passive"))
      (node (ref "K1") (pin "1") (pinfunction "1_1") (pintype "passive"))
      (node (ref "M1") (pin "0") (pinfunction "0_0") (pintype "passive"))
      (node (ref "M1") (pin "10") (pinfunction "10_10") (pintype "passive"))
      (node (ref "M1") (pin "109") (pinfunction "109_109") (pintype "passive"))
      (node (ref "M1") (pin "11") (pinfunction "11_11") (pintype "passive"))
      (node (ref "M1") (pin "110") (pinfunction "110_110") (pintype "passive"))
      (node (ref "M1") (pin "12") (pinfunction "12_12") (pintype "passive"))
      (node (ref "M1") (pin "127") (pinfunction "127_127") (pintype "passive"))
      (node (ref "M1") (pin "128") (pinfunction "128_128") (pintype "passive"))
      (node (ref "M1") (pin "13") (pinfunction "13_13") (pintype "passive"))
      (node (ref "M1") (pin "14") (pinfunction "14_14") (pintype "passive"))
      (node (ref "M1") (pin "141") (pinfunction "141_141") (pintype "passive"))
      (node (ref "M1") (pin "142") (pinfunction "142_142") (pintype "passive"))
      (node (ref "M1") (pin "155") (pinfunction "155_155") (pintype "passive"))
      (node (ref "M1") (pin "156") (pinfunction "156_156") (pintype "passive"))
      (node (ref "M1") (pin "173") (pinfunction "173_173") (pintype "passive"))
      (node (ref "M1") (pin "174") (pinfunction "174_174") (pintype "passive"))
      (node (ref "M1") (pin "187") (pinfunction "187_187") (pintype "passive"))
      (node (ref "M1") (pin "188") (pinfunction "188_188") (pintype "passive"))
      (node (ref "M1") (pin "19") (pinfunction "19_19") (pintype "passive"))
      (node (ref "M1") (pin "20") (pinfunction "20_20") (pintype "passive"))
      (node (ref "M1") (pin "203") (pinfunction "203_203") (pintype "passive"))
      (node (ref "M1") (pin "204") (pinfunction "204_204") (pintype "passive"))
      (node (ref "M1") (pin "37") (pinfunction "37_37") (pintype "passive"))
      (node (ref "M1") (pin "38") (pinfunction "38_38") (pintype "passive"))
      (node (ref "M1") (pin "5") (pinfunction "5_5") (pintype "passive"))
      (node (ref "M1") (pin "55") (pinfunction "55_55") (pintype "passive"))
      (node (ref "M1") (pin "56") (pinfunction "56_56") (pintype "passive"))
      (node (ref "M1") (pin "6") (pinfunction "6_6") (pintype "passive"))
      (node (ref "M1") (pin "73") (pinfunction "73_73") (pintype "passive"))
      (node (ref "M1") (pin "74") (pinfunction "74_74") (pintype "passive"))
      (node (ref "M1") (pin "9") (pinfunction "9_9") (pintype "passive"))
      (node (ref "M1") (pin "91") (pinfunction "91_91") (pintype "passive"))
      (node (ref "M1") (pin "92") (pinfunction "92_92") (pintype "passive"))
      (node (ref "POR") (pin "1") (pinfunction "1_1") (pintype "passive"))
      (node (ref "R14") (pin "1") (pinfunction "1_1") (pintype "passive"))
      (node (ref "R15") (pin "1") (pinfunction "1_1") (pintype "passive"))
      (node (ref "R19") (pin "2") (pinfunction "2_2") (pintype "passive"))
      (node (ref "R20") (pin "2") (pinfunction "2_2") (pintype "passive"))
      (node (ref "R22") (pin "2") (pinfunction "2_2") (pintype "passive"))
      (node (ref "R6") (pin "2") (pinfunction "2_2") (pintype "passive"))
      (node (ref "RST") (pin "1") (pinfunction "1_1") (pintype "passive"))
      (node (ref "U1") (pin "10") (pinfunction "GND_10") (pintype "passive"))
      (node (ref "U1") (pin "11") (pinfunction "GND_11") (pintype "passive"))
      (node (ref "U1") (pin "12") (pinfunction "GND_12") (pintype "passive"))
      (node (ref "U2") (pin "11") (pinfunction "GND_11") (pintype "passive"))
      (node (ref "U3") (pin "8") (pinfunction "GND_8") (pintype "passive"))
      (node (ref "USB1") (pin "0") (pinfunction "GND_0") (pintype "passive"))
      (node (ref "USB1") (pin "1") (pinfunction "GND_1") (pintype "passive"))
      (node (ref "USB1") (pin "6") (pinfunction "GND_6") (pintype "passive"))
    )
    (net (code "177") (name "Net-(BOOT-Pad1)") (class "Default")
      (node (ref "BOOT") (pin "1") (pinfunction "1_1") (pintype "passive"))
      (node (ref "R1") (pin "1") (pinfunction "1_1") (pintype "passive"))
      (node (ref "R4") (pin "1") (pinfunction "1_1") (pintype "passive"))
    )
    (net (code "178") (name "Net-(BOOT-Pad2)") (class "Default")
      (node (ref "BOOT") (pin "2") (pinfunction "2_2") (pintype "passive"))
      (node (ref "R2") (pin "1") (pinfunction "1_1") (pintype "passive"))
      (node (ref "R3") (pin "1") (pinfunction "1_1") (pintype "passive"))
    )
    (net (code "179") (name "Net-(D1-PadK)") (class "Default")
      (node (ref "D1") (pin "K") (pinfunction "K_K") (pintype "passive"))
      (node (ref "R6") (pin "1") (pinfunction "1_1") (pintype "passive"))
    )
    (net (code "180") (name "Net-(L1-Pad2)") (class "Default")
      (node (ref "L1") (pin "2") (pintype "passive"))
      (node (ref "U1") (pin "1") (pinfunction "SW_1") (pintype "passive"))
      (node (ref "U1") (pin "9") (pinfunction "SW_9") (pintype "passive"))
    )
    (net (code "181") (name "Net-(U1-EN)") (class "Default")
      (node (ref "R16") (pin "1") (pinfunction "1_1") (pintype "passive"))
      (node (ref "U1") (pin "5") (pinfunction "EN_5") (pintype "passive"))
    )
    (net (code "182") (name "Net-(U1-FB)") (class "Default")
      (node (ref "C6") (pin "1") (pinfunction "1_1") (pintype "passive"))
      (node (ref "R20") (pin "1") (pinfunction "1_1") (pintype "passive"))
      (node (ref "R21") (pin "1") (pinfunction "1_1") (pintype "passive"))
      (node (ref "U1") (pin "3") (pinfunction "FB_3") (pintype "passive"))
    )
    (net (code "183") (name "Net-(U1-MOD)") (class "Default")
      (node (ref "C3") (pin "1") (pinfunction "1_1") (pintype "passive"))
      (node (ref "U1") (pin "6") (pinfunction "MOD_6") (pintype "passive"))
    )
    (net (code "184") (name "Net-(U1-PG)") (class "Default")
      (node (ref "R5") (pin "1") (pinfunction "1_1") (pintype "passive"))
      (node (ref "U1") (pin "7") (pinfunction "PG_7") (pintype "passive"))
    )
    (net (code "185") (name "Net-(U1-RAMP)") (class "Default")
      (node (ref "C4") (pin "1") (pinfunction "1_1") (pintype "passive"))
      (node (ref "U1") (pin "4") (pinfunction "RAMP_4") (pintype "passive"))
    )
    (net (code "186") (name "Net-(U2-OE)") (class "Default")
      (node (ref "R17") (pin "2") (pinfunction "2_2") (pintype "passive"))
      (node (ref "U2") (pin "10") (pinfunction "OE_10") (pintype "passive"))
    )
    (net (code "187") (name "Net-(U3-KEY)") (class "Default")
      (node (ref "K1") (pin "2") (pinfunction "2_2") (pintype "passive"))
      (node (ref "U3") (pin "3") (pinfunction "KEY_3") (pintype "passive"))
    )
    (net (code "188") (name "Net-(U3-OUT)") (class "Default")
      (node (ref "R19") (pin "1") (pinfunction "1_1") (pintype "passive"))
      (node (ref "U3") (pin "6") (pinfunction "OUT_6") (pintype "passive"))
      (node (ref "U4") (pin "5") (pinfunction "ON_5") (pintype "passive"))
    )
    (net (code "189") (name "Net-(U4-R1{slash}C1)") (class "Default")
      (node (ref "C5") (pin "2") (pinfunction "2_2") (pintype "passive"))
      (node (ref "R18") (pin "1") (pinfunction "1_1") (pintype "passive"))
      (node (ref "U4") (pin "6") (pinfunction "R1/C1_6") (pintype "passive"))
    )
    (net (code "190") (name "Net-(U4-R2)") (class "Default")
      (node (ref "R22") (pin "1") (pinfunction "1_1") (pintype "passive"))
      (node (ref "U4") (pin "1") (pinfunction "R2_1") (pintype "passive"))
    )
    (net (code "191") (name "Net-(USB1-CC1)") (class "Default")
      (node (ref "R14") (pin "2") (pinfunction "2_2") (pintype "passive"))
      (node (ref "USB1") (pin "3") (pinfunction "CC1_3") (pintype "passive"))
    )
    (net (code "192") (name "Net-(USB1-CC2)") (class "Default")
      (node (ref "R15") (pin "2") (pinfunction "2_2") (pintype "passive"))
      (node (ref "USB1") (pin "4") (pinfunction "CC2_4") (pintype "passive"))
    )
    (net (code "193") (name "VBUS") (class "Default")
      (node (ref "C11") (pin "1") (pinfunction "1_1") (pintype "passive"))
      (node (ref "R18") (pin "2") (pinfunction "2_2") (pintype "passive"))
      (node (ref "U3") (pin "1") (pinfunction "VDD_1") (pintype "passive"))
      (node (ref "U4") (pin "4") (pinfunction "VIN_4") (pintype "passive"))
      (node (ref "USB1") (pin "2") (pinfunction "VBUS_2") (pintype "passive"))
      (node (ref "USB1") (pin "5") (pinfunction "VBUS_5") (pintype "passive"))
      (node (ref "VBUS") (pin "1") (pinfunction "1_1") (pintype "passive"))
    )
    (net (code "194") (name "unconnected-(U2-A1-Pad1)") (class "Default")
      (node (ref "U2") (pin "1") (pinfunction "A1_1") (pintype "passive"))
    )
    (net (code "195") (name "unconnected-(U2-A2-Pad3)") (class "Default")
      (node (ref "U2") (pin "3") (pinfunction "A2_3") (pintype "passive"))
    )
    (net (code "196") (name "unconnected-(U2-B1-Pad20)") (class "Default")
      (node (ref "U2") (pin "20") (pinfunction "B1_20") (pintype "passive"))
    )
    (net (code "197") (name "unconnected-(U2-B2-Pad18)") (class "Default")
      (node (ref "U2") (pin "18") (pinfunction "B2_18") (pintype "passive"))
    )
    (net (code "198") (name "unconnected-(U3-NC-Pad2)") (class "Default")
      (node (ref "U3") (pin "2") (pinfunction "NC_2") (pintype "passive"))
    )
    (net (code "199") (name "unconnected-(U3-NC-Pad4)") (class "Default")
      (node (ref "U3") (pin "4") (pinfunction "NC_4") (pintype "passive"))
    )
    (net (code "200") (name "unconnected-(U3-NC-Pad5)") (class "Default")
      (node (ref "U3") (pin "5") (pinfunction "NC_5") (pintype "passive"))
    )
    (net (code "201") (name "unconnected-(U3-NC-Pad7)") (class "Default")
      (node (ref "U3") (pin "7") (pinfunction "NC_7") (pintype "passive"))
    )
  )
)
